# SCH_WINGLET_SD_MMC.net
KiCad netlist of a schematic drawn in Altium Designer
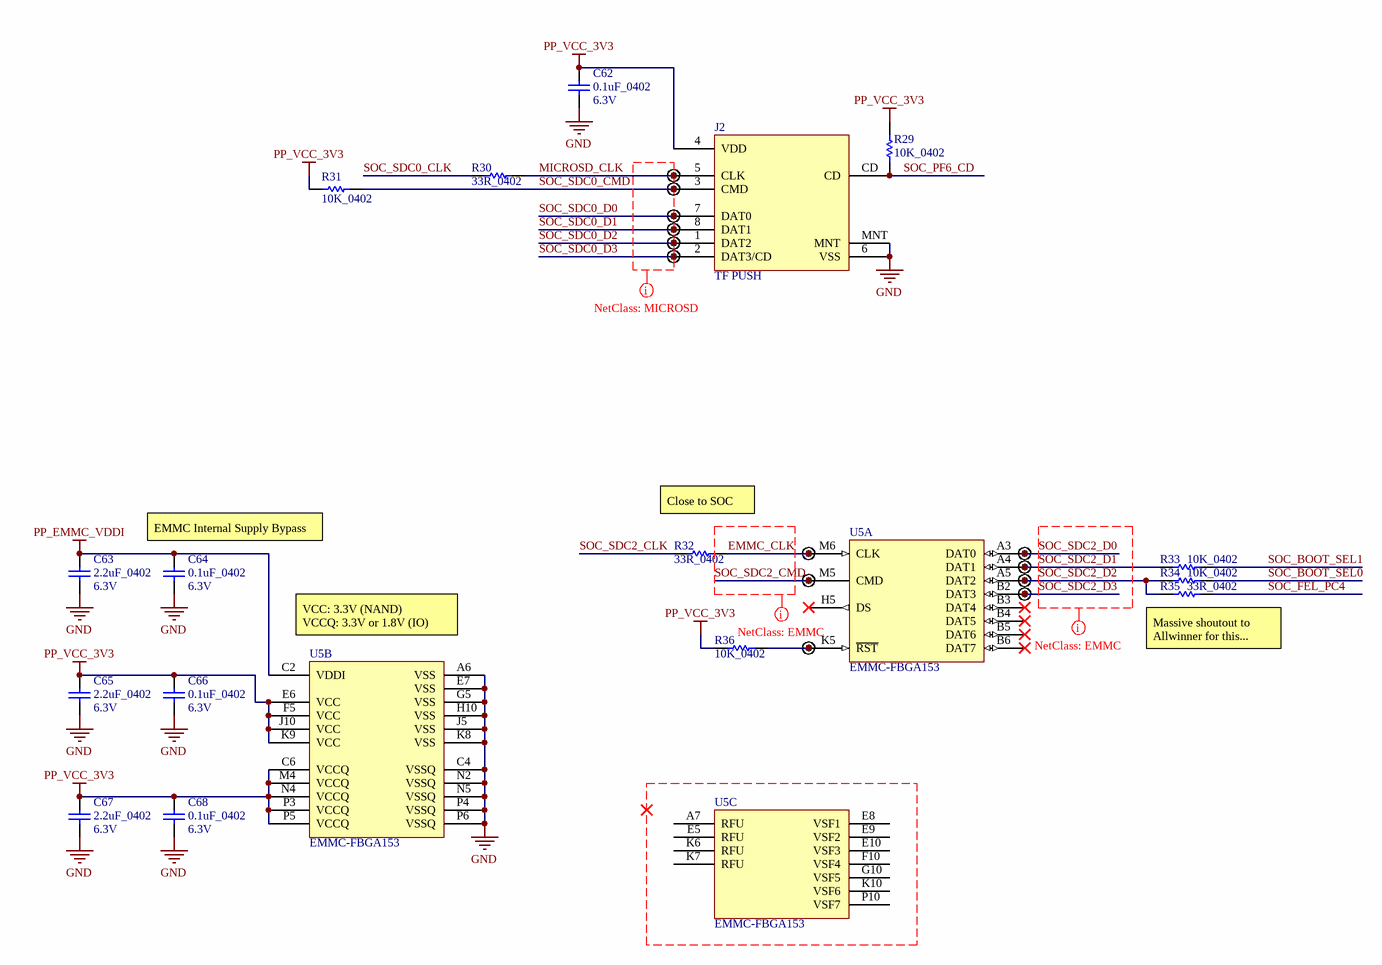
[diagram p0: SCH_WINGLET_SD_MMC.SchDoc]

(export (version "E")
  (design (tool "Eeschema 10.0.6"))
  (components
    (comp (ref "C62")
      (value "0.1uF_0402")
      (footprint "CAPC1005X56X25NL10T15")
      (description "04026D104KAT2A")
      (fields (field (name "MANUFACTURER") "AVX Interconnect / Elco") (field (name "VOLTAGE RATING") "6.3V"))
      (libsource (lib "Altium Content Vault") (part "CAP"))
    )
    (comp (ref "C63")
      (value "2.2uF_0402")
      (footprint "CAPC1005X55X25NL05T10")
      (description "GRM155R60J225ME15D")
      (fields (field (name "MANUFACTURER") "Murata") (field (name "VOLTAGE RATING") "6.3V"))
      (libsource (lib "Altium Content Vault") (part "CAP"))
    )
    (comp (ref "C64")
      (value "0.1uF_0402")
      (footprint "CAPC1005X56X25NL10T15")
      (description "04026D104KAT2A")
      (fields (field (name "MANUFACTURER") "AVX Interconnect / Elco") (field (name "VOLTAGE RATING") "6.3V"))
      (libsource (lib "Altium Content Vault") (part "CAP"))
    )
    (comp (ref "C65")
      (value "2.2uF_0402")
      (footprint "CAPC1005X55X25NL05T10")
      (description "GRM155R60J225ME15D")
      (fields (field (name "MANUFACTURER") "Murata") (field (name "VOLTAGE RATING") "6.3V"))
      (libsource (lib "Altium Content Vault") (part "CAP"))
    )
    (comp (ref "C66")
      (value "0.1uF_0402")
      (footprint "CAPC1005X56X25NL10T15")
      (description "04026D104KAT2A")
      (fields (field (name "MANUFACTURER") "AVX Interconnect / Elco") (field (name "VOLTAGE RATING") "6.3V"))
      (libsource (lib "Altium Content Vault") (part "CAP"))
    )
    (comp (ref "C67")
      (value "2.2uF_0402")
      (footprint "CAPC1005X55X25NL05T10")
      (description "GRM155R60J225ME15D")
      (fields (field (name "MANUFACTURER") "Murata") (field (name "VOLTAGE RATING") "6.3V"))
      (libsource (lib "Altium Content Vault") (part "CAP"))
    )
    (comp (ref "C68")
      (value "0.1uF_0402")
      (footprint "CAPC1005X56X25NL10T15")
      (description "04026D104KAT2A")
      (fields (field (name "MANUFACTURER") "AVX Interconnect / Elco") (field (name "VOLTAGE RATING") "6.3V"))
      (libsource (lib "Altium Content Vault") (part "CAP"))
    )
    (comp (ref "J2")
      (value "TF PUSH")
      (footprint "LCSC_TF_PUSH")
      (description "MicroSD Card Slot Push-Pull")
      (libsource (lib "DCAV32_WINGLET_SCHLIB") (part "SDCARD_TF_PUSH"))
    )
    (comp (ref "R29")
      (value "10K_0402")
      (footprint "RESC1005X40X25NL05T05")
      (fields (field (name "TOLERANCE") "1%") (field (name "MANUFACTURER") "Panasonic"))
      (libsource (lib "Altium Content Vault") (part "RES-2"))
    )
    (comp (ref "R30")
      (value "33R_0402")
      (footprint "RESC1005X40X25NL05T05")
      (description "ERJ2RKF33R0X")
      (fields (field (name "MANUFACTURER") "Panasonic"))
      (libsource (lib "Altium Content Vault") (part "RES"))
    )
    (comp (ref "R31")
      (value "10K_0402")
      (footprint "RESC1005X40X25NL05T05")
      (fields (field (name "TOLERANCE") "1%") (field (name "MANUFACTURER") "Panasonic"))
      (libsource (lib "Altium Content Vault") (part "RES-2"))
    )
    (comp (ref "R32")
      (value "33R_0402")
      (footprint "RESC1005X40X25NL05T05")
      (description "ERJ2RKF33R0X")
      (fields (field (name "MANUFACTURER") "Panasonic"))
      (libsource (lib "Altium Content Vault") (part "RES"))
    )
    (comp (ref "R33")
      (value "10K_0402")
      (footprint "RESC1005X40X25NL05T05")
      (fields (field (name "TOLERANCE") "1%") (field (name "MANUFACTURER") "Panasonic"))
      (libsource (lib "Altium Content Vault") (part "RES-2"))
    )
    (comp (ref "R34")
      (value "10K_0402")
      (footprint "RESC1005X40X25NL05T05")
      (fields (field (name "TOLERANCE") "1%") (field (name "MANUFACTURER") "Panasonic"))
      (libsource (lib "Altium Content Vault") (part "RES-2"))
    )
    (comp (ref "R35")
      (value "33R_0402")
      (footprint "RESC1005X40X25NL05T05")
      (description "ERJ2RKF33R0X")
      (fields (field (name "MANUFACTURER") "Panasonic"))
      (libsource (lib "Altium Content Vault") (part "RES"))
    )
    (comp (ref "R36")
      (value "10K_0402")
      (footprint "RESC1005X40X25NL05T05")
      (fields (field (name "TOLERANCE") "1%") (field (name "MANUFACTURER") "Panasonic"))
      (libsource (lib "Altium Content Vault") (part "RES-2"))
    )
    (comp (ref "TP12")
      (value "TESTPOINT")
      (footprint "TESTPOINT-0.7MM-SINGLE-LAYER")
      (description "TESTPOINT SINGLE LAYER 0.7MM")
      (libsource (lib "DCAV32_WINGLET_SCHLIB") (part "TP_07"))
    )
    (comp (ref "TP13")
      (value "TESTPOINT")
      (footprint "TESTPOINT-0.7MM-SINGLE-LAYER")
      (description "TESTPOINT SINGLE LAYER 0.7MM")
      (libsource (lib "DCAV32_WINGLET_SCHLIB") (part "TP_07"))
    )
    (comp (ref "TP14")
      (value "TESTPOINT")
      (footprint "TESTPOINT-0.7MM-SINGLE-LAYER")
      (description "TESTPOINT SINGLE LAYER 0.7MM")
      (libsource (lib "DCAV32_WINGLET_SCHLIB") (part "TP_07"))
    )
    (comp (ref "TP15")
      (value "TESTPOINT")
      (footprint "TESTPOINT-0.7MM-SINGLE-LAYER")
      (description "TESTPOINT SINGLE LAYER 0.7MM")
      (libsource (lib "DCAV32_WINGLET_SCHLIB") (part "TP_07"))
    )
    (comp (ref "TP16")
      (value "TESTPOINT")
      (footprint "TESTPOINT-0.7MM-SINGLE-LAYER")
      (description "TESTPOINT SINGLE LAYER 0.7MM")
      (libsource (lib "DCAV32_WINGLET_SCHLIB") (part "TP_07"))
    )
    (comp (ref "TP17")
      (value "TESTPOINT")
      (footprint "TESTPOINT-0.7MM-SINGLE-LAYER")
      (description "TESTPOINT SINGLE LAYER 0.7MM")
      (libsource (lib "DCAV32_WINGLET_SCHLIB") (part "TP_07"))
    )
    (comp (ref "TP18")
      (value "TESTPOINT")
      (footprint "TESTPOINT-0.7MM-SINGLE-LAYER")
      (description "TESTPOINT SINGLE LAYER 0.7MM")
      (libsource (lib "DCAV32_WINGLET_SCHLIB") (part "TP_07"))
    )
    (comp (ref "TP19")
      (value "TESTPOINT")
      (footprint "TESTPOINT-0.7MM-SINGLE-LAYER")
      (description "TESTPOINT SINGLE LAYER 0.7MM")
      (libsource (lib "DCAV32_WINGLET_SCHLIB") (part "TP_07"))
    )
    (comp (ref "TP20")
      (value "TESTPOINT")
      (footprint "TESTPOINT-0.7MM-SINGLE-LAYER")
      (description "TESTPOINT SINGLE LAYER 0.7MM")
      (libsource (lib "DCAV32_WINGLET_SCHLIB") (part "TP_07"))
    )
    (comp (ref "TP21")
      (value "TESTPOINT")
      (footprint "TESTPOINT-0.7MM-SINGLE-LAYER")
      (description "TESTPOINT SINGLE LAYER 0.7MM")
      (libsource (lib "DCAV32_WINGLET_SCHLIB") (part "TP_07"))
    )
    (comp (ref "TP22")
      (value "TESTPOINT")
      (footprint "TESTPOINT-0.7MM-SINGLE-LAYER")
      (description "TESTPOINT SINGLE LAYER 0.7MM")
      (libsource (lib "DCAV32_WINGLET_SCHLIB") (part "TP_07"))
    )
    (comp (ref "TP23")
      (value "TESTPOINT")
      (footprint "TESTPOINT-0.7MM-SINGLE-LAYER")
      (description "TESTPOINT SINGLE LAYER 0.7MM")
      (libsource (lib "DCAV32_WINGLET_SCHLIB") (part "TP_07"))
    )
    (comp (ref "TP24")
      (value "TESTPOINT")
      (footprint "TESTPOINT-0.7MM-SINGLE-LAYER")
      (description "TESTPOINT SINGLE LAYER 0.7MM")
      (libsource (lib "DCAV32_WINGLET_SCHLIB") (part "TP_07"))
    )
    (comp (ref "U5")
      (value "EMMC-FBGA153")
      (footprint "BGA153C50P14X14_1150X1300X100")
      (description "FLASH - NAND (MLC) Memory IC 32Gb (4G x 8) eMMC 5.1 153-FBGA (11.5x13)")
      (libsource (lib "DCAV32_WINGLET_SCHLIB") (part "EMMC-FBGA153"))
    )
  )
  (nets
    (net (code "1") (name "/EMMC_CLK") (class "Default")
      (node (ref "R32") (pin "2") (pinfunction "2_2") (pintype "passive"))
      (node (ref "TP18") (pin "1") (pinfunction "1_1") (pintype "passive"))
      (node (ref "U5") (pin "M6") (pinfunction "CLK_M6") (pintype "input"))
    )
    (net (code "2") (name "/MICROSD_CLK") (class "Default")
      (node (ref "J2") (pin "5") (pinfunction "CLK_5") (pintype "passive"))
      (node (ref "R30") (pin "2") (pinfunction "2_2") (pintype "passive"))
      (node (ref "TP12") (pin "1") (pinfunction "1_1") (pintype "passive"))
    )
    (net (code "3") (name "/SOC_BOOT_SEL0") (class "Default")
      (node (ref "R34") (pin "2") (pinfunction "2_2") (pintype "passive"))
    )
    (net (code "4") (name "/SOC_BOOT_SEL1") (class "Default")
      (node (ref "R33") (pin "2") (pinfunction "2_2") (pintype "passive"))
    )
    (net (code "5") (name "/SOC_FEL_PC4") (class "Default")
      (node (ref "R35") (pin "2") (pinfunction "2_2") (pintype "passive"))
    )
    (net (code "6") (name "/SOC_PF6_CD") (class "Default")
      (node (ref "J2") (pin "CD") (pinfunction "CD_CD") (pintype "passive"))
      (node (ref "R29") (pin "2") (pinfunction "2_2") (pintype "passive"))
    )
    (net (code "7") (name "/SOC_SDC0_CLK") (class "Default")
      (node (ref "R30") (pin "1") (pinfunction "1_1") (pintype "passive"))
    )
    (net (code "8") (name "/SOC_SDC0_CMD") (class "Default")
      (node (ref "J2") (pin "3") (pinfunction "CMD_3") (pintype "passive"))
      (node (ref "R31") (pin "2") (pinfunction "2_2") (pintype "passive"))
      (node (ref "TP13") (pin "1") (pinfunction "1_1") (pintype "passive"))
    )
    (net (code "9") (name "/SOC_SDC0_D0") (class "Default")
      (node (ref "J2") (pin "7") (pinfunction "DAT0_7") (pintype "passive"))
      (node (ref "TP14") (pin "1") (pinfunction "1_1") (pintype "passive"))
    )
    (net (code "10") (name "/SOC_SDC0_D1") (class "Default")
      (node (ref "J2") (pin "8") (pinfunction "DAT1_8") (pintype "passive"))
      (node (ref "TP15") (pin "1") (pinfunction "1_1") (pintype "passive"))
    )
    (net (code "11") (name "/SOC_SDC0_D2") (class "Default")
      (node (ref "J2") (pin "1") (pinfunction "DAT2_1") (pintype "passive"))
      (node (ref "TP16") (pin "1") (pinfunction "1_1") (pintype "passive"))
    )
    (net (code "12") (name "/SOC_SDC0_D3") (class "Default")
      (node (ref "J2") (pin "2") (pinfunction "DAT3/CD_2") (pintype "passive"))
      (node (ref "TP17") (pin "1") (pinfunction "1_1") (pintype "passive"))
    )
    (net (code "13") (name "/SOC_SDC2_CLK") (class "Default")
      (node (ref "R32") (pin "1") (pinfunction "1_1") (pintype "passive"))
    )
    (net (code "14") (name "/SOC_SDC2_CMD") (class "Default")
      (node (ref "TP21") (pin "1") (pinfunction "1_1") (pintype "passive"))
      (node (ref "U5") (pin "M5") (pinfunction "CMD_M5") (pintype "passive"))
    )
    (net (code "15") (name "/SOC_SDC2_D0") (class "Default")
      (node (ref "TP19") (pin "1") (pinfunction "1_1") (pintype "passive"))
      (node (ref "U5") (pin "A3") (pinfunction "DAT0_A3") (pintype "bidirectional"))
    )
    (net (code "16") (name "/SOC_SDC2_D1") (class "Default")
      (node (ref "R33") (pin "1") (pinfunction "1_1") (pintype "passive"))
      (node (ref "TP20") (pin "1") (pinfunction "1_1") (pintype "passive"))
      (node (ref "U5") (pin "A4") (pinfunction "DAT1_A4") (pintype "bidirectional"))
    )
    (net (code "17") (name "/SOC_SDC2_D2") (class "Default")
      (node (ref "R34") (pin "1") (pinfunction "1_1") (pintype "passive"))
      (node (ref "R35") (pin "1") (pinfunction "1_1") (pintype "passive"))
      (node (ref "TP22") (pin "1") (pinfunction "1_1") (pintype "passive"))
      (node (ref "U5") (pin "A5") (pinfunction "DAT2_A5") (pintype "bidirectional"))
    )
    (net (code "18") (name "/SOC_SDC2_D3") (class "Default")
      (node (ref "TP23") (pin "1") (pinfunction "1_1") (pintype "passive"))
      (node (ref "U5") (pin "B2") (pinfunction "DAT3_B2") (pintype "bidirectional"))
    )
    (net (code "19") (name "GND") (class "Default")
      (node (ref "C62") (pin "1") (pinfunction "1_1") (pintype "passive"))
      (node (ref "C63") (pin "1") (pinfunction "1_1") (pintype "passive"))
      (node (ref "C64") (pin "1") (pinfunction "1_1") (pintype "passive"))
      (node (ref "C65") (pin "1") (pinfunction "1_1") (pintype "passive"))
      (node (ref "C66") (pin "1") (pinfunction "1_1") (pintype "passive"))
      (node (ref "C67") (pin "1") (pinfunction "1_1") (pintype "passive"))
      (node (ref "C68") (pin "1") (pinfunction "1_1") (pintype "passive"))
      (node (ref "J2") (pin "6") (pinfunction "VSS_6") (pintype "passive"))
      (node (ref "J2") (pin "MNT") (pinfunction "MNT_MNT") (pintype "passive"))
      (node (ref "U5") (pin "A6") (pinfunction "VSS_A6") (pintype "power_in"))
      (node (ref "U5") (pin "C4") (pinfunction "VSSQ_C4") (pintype "power_in"))
      (node (ref "U5") (pin "E7") (pinfunction "VSS_E7") (pintype "power_in"))
      (node (ref "U5") (pin "G5") (pinfunction "VSS_G5") (pintype "power_in"))
      (node (ref "U5") (pin "H10") (pinfunction "VSS_H10") (pintype "power_in"))
      (node (ref "U5") (pin "J5") (pinfunction "VSS_J5") (pintype "power_in"))
      (node (ref "U5") (pin "K8") (pinfunction "VSS_K8") (pintype "power_in"))
      (node (ref "U5") (pin "N2") (pinfunction "VSSQ_N2") (pintype "power_in"))
      (node (ref "U5") (pin "N5") (pinfunction "VSSQ_N5") (pintype "power_in"))
      (node (ref "U5") (pin "P4") (pinfunction "VSSQ_P4") (pintype "power_in"))
      (node (ref "U5") (pin "P6") (pinfunction "VSSQ_P6") (pintype "power_in"))
    )
    (net (code "20") (name "Net-(U5A-~{RST})") (class "Default")
      (node (ref "R36") (pin "1") (pinfunction "1_1") (pintype "passive"))
      (node (ref "TP24") (pin "1") (pinfunction "1_1") (pintype "passive"))
      (node (ref "U5") (pin "K5") (pinfunction "~{RST}_K5") (pintype "input"))
    )
    (net (code "21") (name "PP_EMMC_VDDI") (class "Default")
      (node (ref "C63") (pin "2") (pinfunction "2_2") (pintype "passive"))
      (node (ref "C64") (pin "2") (pinfunction "2_2") (pintype "passive"))
      (node (ref "U5") (pin "C2") (pinfunction "VDDI_C2") (pintype "power_in"))
    )
    (net (code "22") (name "PP_VCC_3V3") (class "Default")
      (node (ref "C62") (pin "2") (pinfunction "2_2") (pintype "passive"))
      (node (ref "C65") (pin "2") (pinfunction "2_2") (pintype "passive"))
      (node (ref "C66") (pin "2") (pinfunction "2_2") (pintype "passive"))
      (node (ref "C67") (pin "2") (pinfunction "2_2") (pintype "passive"))
      (node (ref "C68") (pin "2") (pinfunction "2_2") (pintype "passive"))
      (node (ref "J2") (pin "4") (pinfunction "VDD_4") (pintype "passive"))
      (node (ref "R29") (pin "1") (pinfunction "1_1") (pintype "passive"))
      (node (ref "R31") (pin "1") (pinfunction "1_1") (pintype "passive"))
      (node (ref "R36") (pin "2") (pinfunction "2_2") (pintype "passive"))
      (node (ref "U5") (pin "C6") (pinfunction "VCCQ_C6") (pintype "power_in"))
      (node (ref "U5") (pin "E6") (pinfunction "VCC_E6") (pintype "power_in"))
      (node (ref "U5") (pin "F5") (pinfunction "VCC_F5") (pintype "power_in"))
      (node (ref "U5") (pin "J10") (pinfunction "VCC_J10") (pintype "power_in"))
      (node (ref "U5") (pin "K9") (pinfunction "VCC_K9") (pintype "power_in"))
      (node (ref "U5") (pin "M4") (pinfunction "VCCQ_M4") (pintype "power_in"))
      (node (ref "U5") (pin "N4") (pinfunction "VCCQ_N4") (pintype "power_in"))
      (node (ref "U5") (pin "P3") (pinfunction "VCCQ_P3") (pintype "power_in"))
      (node (ref "U5") (pin "P5") (pinfunction "VCCQ_P5") (pintype "power_in"))
    )
    (net (code "23") (name "unconnected-(U5A-DAT4-PadB3)") (class "Default")
      (node (ref "U5") (pin "B3") (pinfunction "DAT4_B3") (pintype "bidirectional+no_connect"))
    )
    (net (code "24") (name "unconnected-(U5A-DAT5-PadB4)") (class "Default")
      (node (ref "U5") (pin "B4") (pinfunction "DAT5_B4") (pintype "bidirectional+no_connect"))
    )
    (net (code "25") (name "unconnected-(U5A-DAT6-PadB5)") (class "Default")
      (node (ref "U5") (pin "B5") (pinfunction "DAT6_B5") (pintype "bidirectional+no_connect"))
    )
    (net (code "26") (name "unconnected-(U5A-DAT7-PadB6)") (class "Default")
      (node (ref "U5") (pin "B6") (pinfunction "DAT7_B6") (pintype "bidirectional+no_connect"))
    )
    (net (code "27") (name "unconnected-(U5A-DS-PadH5)") (class "Default")
      (node (ref "U5") (pin "H5") (pinfunction "DS_H5") (pintype "output+no_connect"))
    )
    (net (code "28") (name "unconnected-(U5C-RFU-PadA7)") (class "Default")
      (node (ref "U5") (pin "A7") (pinfunction "RFU_A7") (pintype "tri_state"))
    )
    (net (code "29") (name "unconnected-(U5C-RFU-PadE5)") (class "Default")
      (node (ref "U5") (pin "E5") (pinfunction "RFU_E5") (pintype "tri_state"))
    )
    (net (code "30") (name "unconnected-(U5C-RFU-PadK6)") (class "Default")
      (node (ref "U5") (pin "K6") (pinfunction "RFU_K6") (pintype "tri_state"))
    )
    (net (code "31") (name "unconnected-(U5C-RFU-PadK7)") (class "Default")
      (node (ref "U5") (pin "K7") (pinfunction "RFU_K7") (pintype "tri_state"))
    )
    (net (code "32") (name "unconnected-(U5C-VSF1-PadE8)") (class "Default")
      (node (ref "U5") (pin "E8") (pinfunction "VSF1_E8") (pintype "tri_state"))
    )
    (net (code "33") (name "unconnected-(U5C-VSF2-PadE9)") (class "Default")
      (node (ref "U5") (pin "E9") (pinfunction "VSF2_E9") (pintype "tri_state"))
    )
    (net (code "34") (name "unconnected-(U5C-VSF3-PadE10)") (class "Default")
      (node (ref "U5") (pin "E10") (pinfunction "VSF3_E10") (pintype "tri_state"))
    )
    (net (code "35") (name "unconnected-(U5C-VSF4-PadF10)") (class "Default")
      (node (ref "U5") (pin "F10") (pinfunction "VSF4_F10") (pintype "tri_state"))
    )
    (net (code "36") (name "unconnected-(U5C-VSF5-PadG10)") (class "Default")
      (node (ref "U5") (pin "G10") (pinfunction "VSF5_G10") (pintype "tri_state"))
    )
    (net (code "37") (name "unconnected-(U5C-VSF6-PadK10)") (class "Default")
      (node (ref "U5") (pin "K10") (pinfunction "VSF6_K10") (pintype "tri_state"))
    )
    (net (code "38") (name "unconnected-(U5C-VSF7-PadP10)") (class "Default")
      (node (ref "U5") (pin "P10") (pinfunction "VSF7_P10") (pintype "tri_state"))
    )
  )
)
